# SCH_CatDoor_2024-03-03.net
KiCad netlist of a schematic drawn in EasyEDA
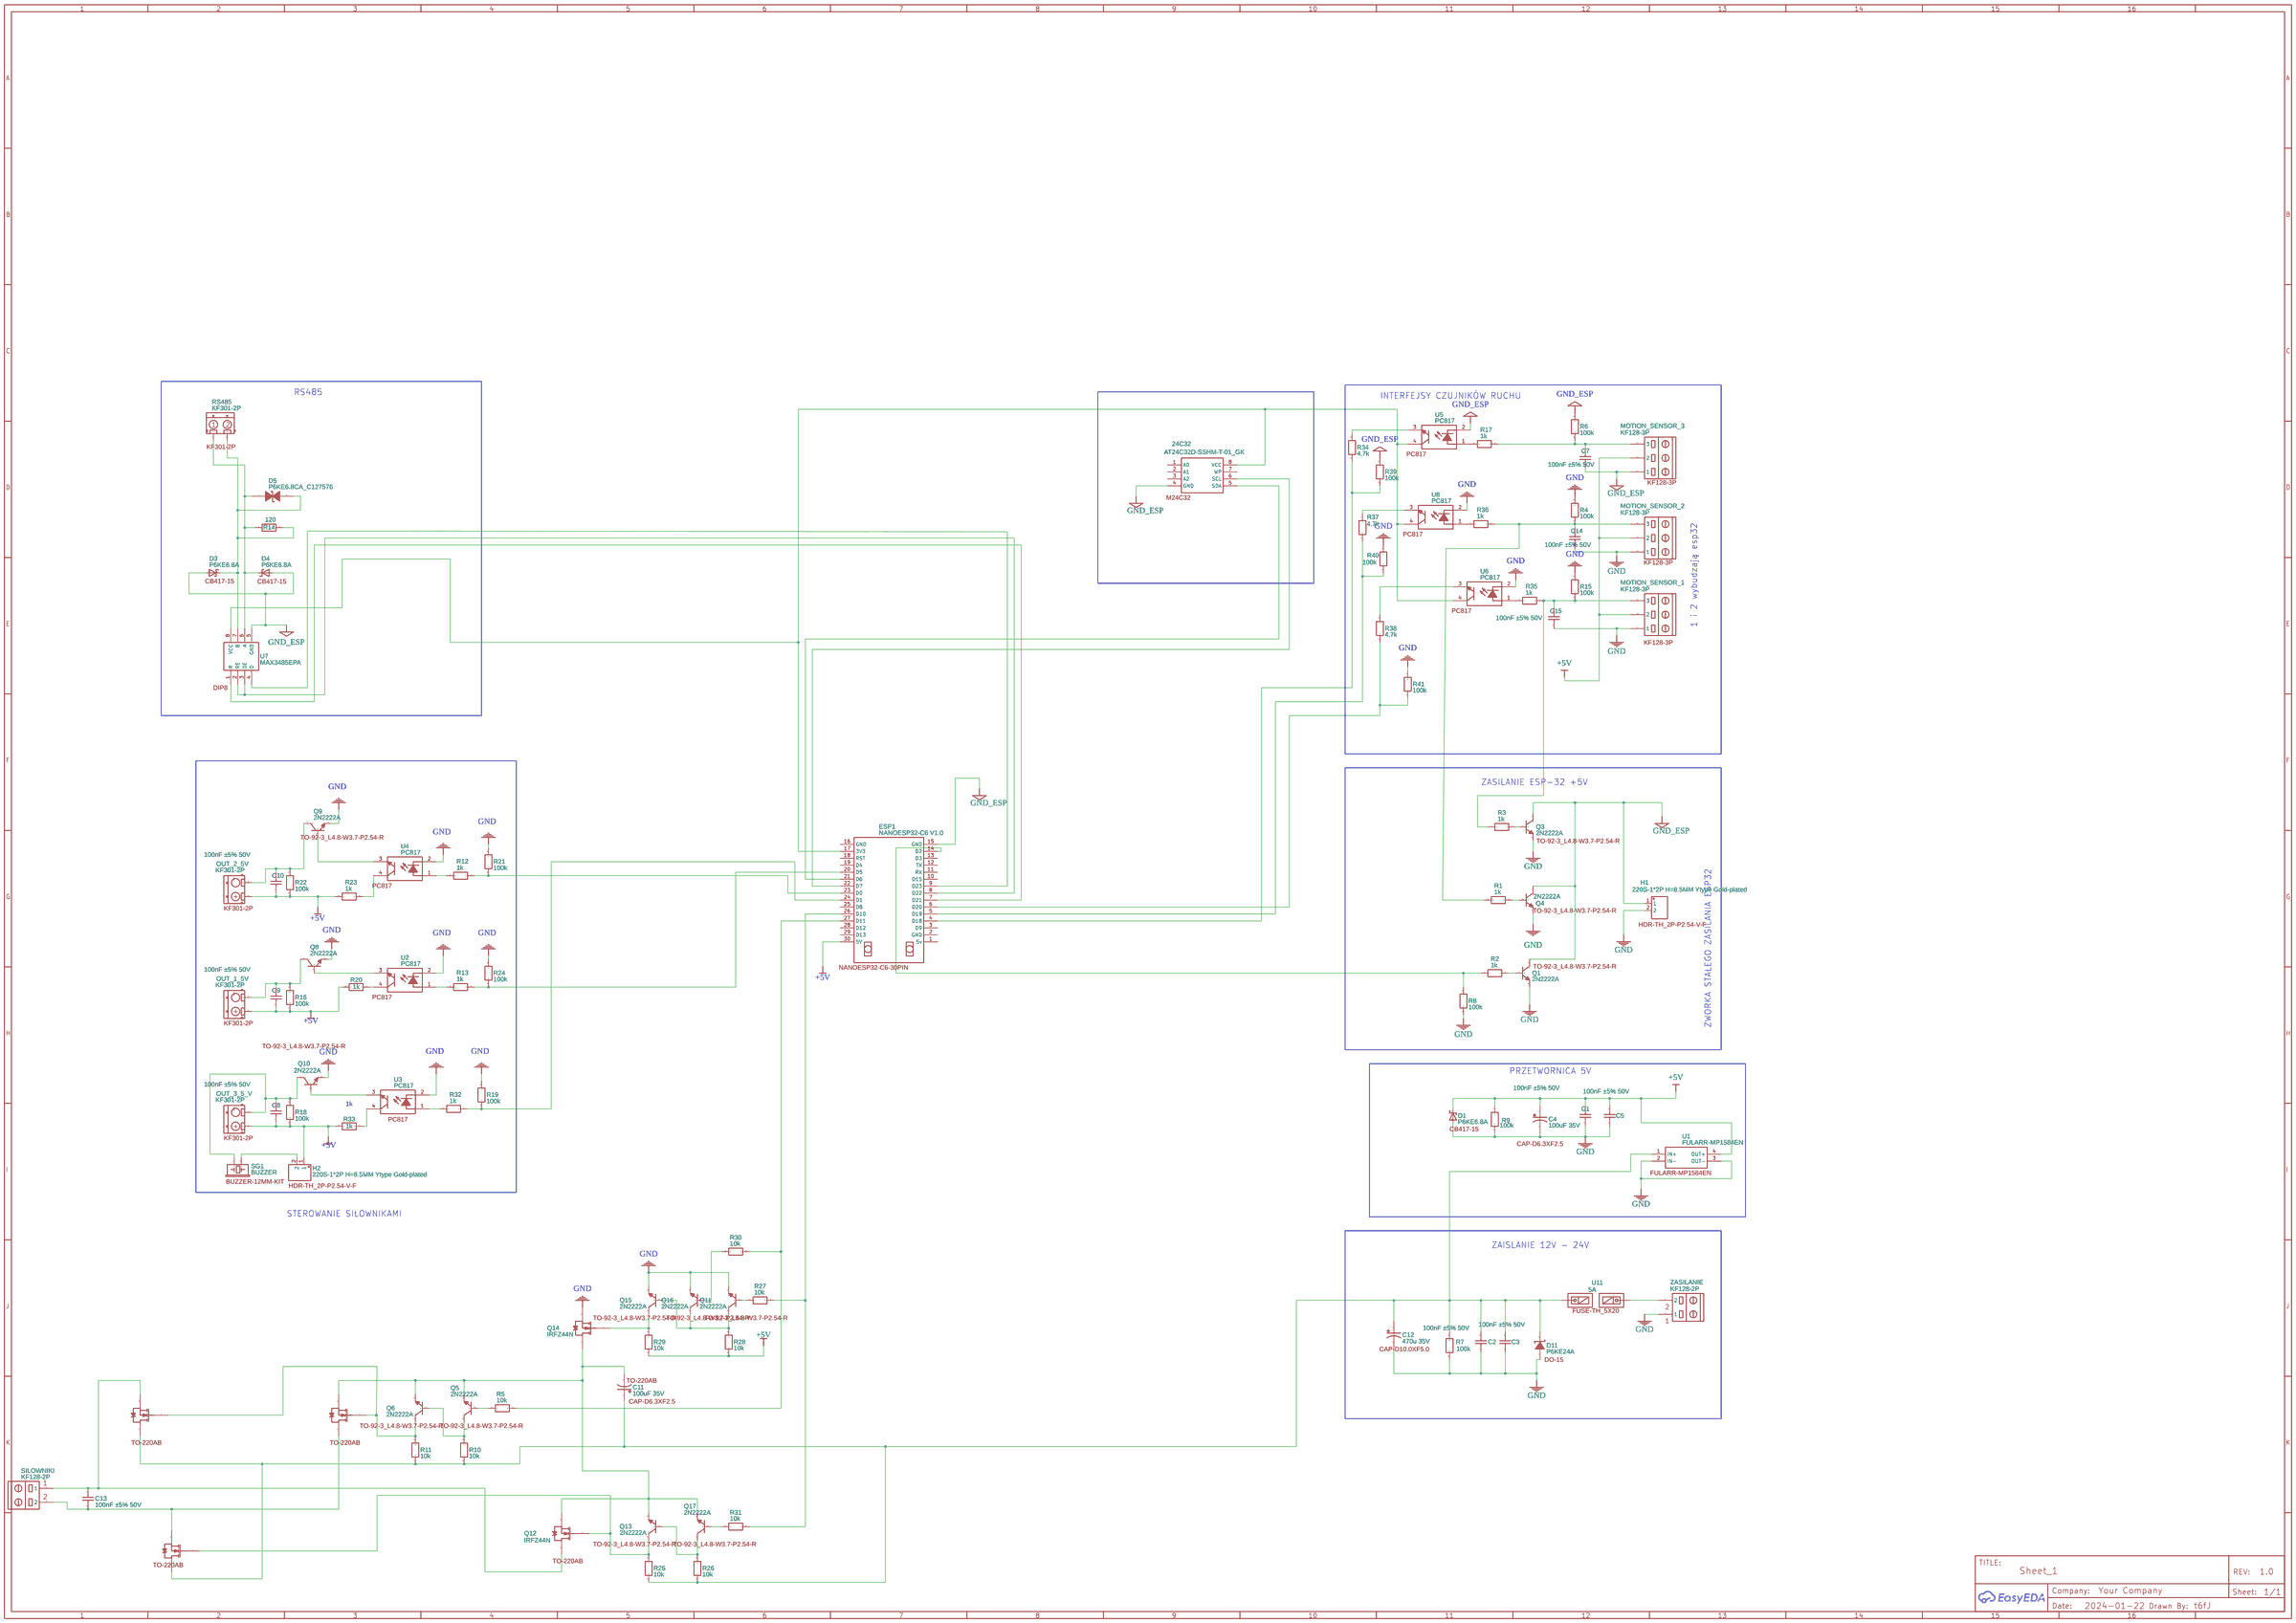
[diagram p0: schematic sheet]

(export (version "E")
  (design (tool "Eeschema 10.0.6"))
  (components
    (comp (ref "24C32")
      (value "AT24C32D-SSHM-T-01_GK")
      (fields (field (name "Manufacturer Part") "AT24C32D-SSHM-T") (field (name "Manufacturer") "MICROCHIP"))
      (libsource (lib "") (part "AT24C32D-SSHM-T-01_GK"))
    )
    (comp (ref "C1")
      (value "100nF ±5% 50V")
      (fields
        (field (name "Manufacturer Part") "10nF(103) ±5% 100V")
        (field (name "Manufacturer") "ReliaPro")
      )
      (libsource (lib "") (part "10nF(103) ±5% 100V"))
    )
    (comp (ref "C2")
      (value "100nF ±5% 50V")
      (fields
        (field (name "Manufacturer Part") "10nF(103) ±5% 100V")
        (field (name "Manufacturer") "ReliaPro")
      )
      (libsource (lib "") (part "10nF(103) ±5% 100V"))
    )
    (comp (ref "C3")
      (value "100nF ±5% 50V")
      (fields
        (field (name "Manufacturer Part") "10nF(103) ±5% 100V")
        (field (name "Manufacturer") "ReliaPro")
      )
      (libsource (lib "") (part "10nF(103) ±5% 100V"))
    )
    (comp (ref "C4") (value "100uF 35V") (libsource (lib "") (part "Cap_Electrolytic(TH)_D6.3XF2.5_US")))
    (comp (ref "C5")
      (value "100nF ±5% 50V")
      (fields
        (field (name "Manufacturer Part") "10nF(103) ±5% 100V")
        (field (name "Manufacturer") "ReliaPro")
      )
      (libsource (lib "") (part "10nF(103) ±5% 100V"))
    )
    (comp (ref "C7")
      (value "100nF ±5% 50V")
      (fields
        (field (name "Manufacturer Part") "10nF(103) ±5% 100V")
        (field (name "Manufacturer") "ReliaPro")
      )
      (libsource (lib "") (part "10nF(103) ±5% 100V"))
    )
    (comp (ref "C8")
      (value "100nF ±5% 50V")
      (fields
        (field (name "Manufacturer Part") "10nF(103) ±5% 100V")
        (field (name "Manufacturer") "ReliaPro")
      )
      (libsource (lib "") (part "10nF(103) ±5% 100V"))
    )
    (comp (ref "C9")
      (value "100nF ±5% 50V")
      (fields
        (field (name "Manufacturer Part") "10nF(103) ±5% 100V")
        (field (name "Manufacturer") "ReliaPro")
      )
      (libsource (lib "") (part "10nF(103) ±5% 100V"))
    )
    (comp (ref "C10")
      (value "100nF ±5% 50V")
      (fields
        (field (name "Manufacturer Part") "10nF(103) ±5% 100V")
        (field (name "Manufacturer") "ReliaPro")
      )
      (libsource (lib "") (part "10nF(103) ±5% 100V"))
    )
    (comp (ref "C11") (value "100uF 35V") (libsource (lib "") (part "Cap_Electrolytic(TH)_D6.3XF2.5_US_1")))
    (comp (ref "C12") (value "470u 35V") (libsource (lib "") (part "Cap_Electrolytic(TH)_D10.0XF5.0_US")))
    (comp (ref "C13")
      (value "100nF ±5% 50V")
      (fields
        (field (name "Manufacturer Part") "10nF(103) ±5% 100V")
        (field (name "Manufacturer") "ReliaPro")
      )
      (libsource (lib "") (part "10nF(103) ±5% 100V_1"))
    )
    (comp (ref "C14")
      (value "100nF ±5% 50V")
      (fields
        (field (name "Manufacturer Part") "10nF(103) ±5% 100V")
        (field (name "Manufacturer") "ReliaPro")
      )
      (libsource (lib "") (part "10nF(103) ±5% 100V"))
    )
    (comp (ref "C15")
      (value "100nF ±5% 50V")
      (fields
        (field (name "Manufacturer Part") "10nF(103) ±5% 100V")
        (field (name "Manufacturer") "ReliaPro")
      )
      (libsource (lib "") (part "10nF(103) ±5% 100V"))
    )
    (comp (ref "D1") (value "P6KE6.8A") (libsource (lib "") (part "P6KEXX")))
    (comp (ref "D3") (value "P6KE6.8A") (libsource (lib "") (part "P6KEXX_2")))
    (comp (ref "D4") (value "P6KE6.8A") (libsource (lib "") (part "P6KEXX_1")))
    (comp (ref "D5")
      (value "P6KE6.8CA_C127576")
      (fields (field (name "Manufacturer Part") "P6KE6.8CA") (field (name "Manufacturer") "Yenji"))
      (libsource (lib "") (part "P6KE6.8CA_C127576"))
    )
    (comp (ref "D11")
      (value "P6KE24A")
      (fields (field (name "Manufacturer Part") "P6KE30A") (field (name "Manufacturer") "STMicroelectronics"))
      (libsource (lib "") (part "P6KE30A_C133726"))
    )
    (comp (ref "ESP1") (value "NANOESP32-C6 V1.0") (libsource (lib "") (part "NANOESP32-C6 V1.0")))
    (comp (ref "H1")
      (value "220S-1*2P H=8.5MM Ytype Gold-plated")
      (fields (field (name "Manufacturer Part") "B-2200S02P-A120") (field (name "Manufacturer") "Ckmtw(灿科盟)"))
      (libsource (lib "") (part "220S-1*2P H=8.5MM Ytype Gold-plated_1"))
    )
    (comp (ref "H2")
      (value "220S-1*2P H=8.5MM Ytype Gold-plated")
      (fields (field (name "Manufacturer Part") "B-2200S02P-A120") (field (name "Manufacturer") "Ckmtw(灿科盟)"))
      (libsource (lib "") (part "220S-1*2P H=8.5MM Ytype Gold-plated"))
    )
    (comp (ref "MOTION_SENSOR_1")
      (value "KF128-3P")
      (fields (field (name "Manufacturer Part") "P?"))
      (libsource (lib "") (part "KF128-3P"))
    )
    (comp (ref "MOTION_SENSOR_2")
      (value "KF128-3P")
      (fields (field (name "Manufacturer Part") "P?"))
      (libsource (lib "") (part "KF128-3P_1"))
    )
    (comp (ref "MOTION_SENSOR_3")
      (value "KF128-3P")
      (fields (field (name "Manufacturer Part") "P?"))
      (libsource (lib "") (part "KF128-3P_2"))
    )
    (comp (ref "OUT_1_5V") (value "KF301-2P") (libsource (lib "") (part "KF301-2P")))
    (comp (ref "OUT_2_5V") (value "KF301-2P") (libsource (lib "") (part "KF301-2P_3")))
    (comp (ref "OUT_3_5_V") (value "KF301-2P") (libsource (lib "") (part "KF301-2P_2")))
    (comp (ref "Q1")
      (value "2N2222A")
      (fields (field (name "Manufacturer") "Foshan Blue Rocket Elec"))
      (libsource (lib "") (part "2N2222A"))
    )
    (comp (ref "Q2") (value "IRFZ44N") (libsource (lib "") (part "IRF1404_1")))
    (comp (ref "Q3")
      (value "2N2222A")
      (fields (field (name "Manufacturer") "Foshan Blue Rocket Elec"))
      (libsource (lib "") (part "2N2222A_6"))
    )
    (comp (ref "Q4")
      (value "2N2222A")
      (fields (field (name "Manufacturer") "Foshan Blue Rocket Elec"))
      (libsource (lib "") (part "2N2222A_5"))
    )
    (comp (ref "Q5")
      (value "2N2222A")
      (fields (field (name "Manufacturer") "Foshan Blue Rocket Elec"))
      (libsource (lib "") (part "2N2222A_1"))
    )
    (comp (ref "Q6")
      (value "2N2222A")
      (fields (field (name "Manufacturer") "Foshan Blue Rocket Elec"))
      (libsource (lib "") (part "2N2222A_3"))
    )
    (comp (ref "Q7") (value "IRFZ44N") (libsource (lib "") (part "IRF1404_1")))
    (comp (ref "Q8")
      (value "2N2222A")
      (fields (field (name "Manufacturer") "Foshan Blue Rocket Elec"))
      (libsource (lib "") (part "2N2222A_7"))
    )
    (comp (ref "Q9")
      (value "2N2222A")
      (fields (field (name "Manufacturer") "Foshan Blue Rocket Elec"))
      (libsource (lib "") (part "2N2222A_2"))
    )
    (comp (ref "Q10")
      (value "2N2222A")
      (fields (field (name "Manufacturer") "Foshan Blue Rocket Elec"))
      (libsource (lib "") (part "2N2222A_4"))
    )
    (comp (ref "Q11")
      (value "2N2222A")
      (fields (field (name "Manufacturer") "Foshan Blue Rocket Elec"))
      (libsource (lib "") (part "2N2222A_1"))
    )
    (comp (ref "Q12") (value "IRFZ44N") (libsource (lib "") (part "IRF1404_1")))
    (comp (ref "Q13")
      (value "2N2222A")
      (fields (field (name "Manufacturer") "Foshan Blue Rocket Elec"))
      (libsource (lib "") (part "2N2222A_3"))
    )
    (comp (ref "Q14") (value "IRFZ44N") (libsource (lib "") (part "IRF1404_2")))
    (comp (ref "Q15")
      (value "2N2222A")
      (fields (field (name "Manufacturer") "Foshan Blue Rocket Elec"))
      (libsource (lib "") (part "2N2222A_3"))
    )
    (comp (ref "Q16")
      (value "2N2222A")
      (fields (field (name "Manufacturer") "Foshan Blue Rocket Elec"))
      (libsource (lib "") (part "2N2222A_1"))
    )
    (comp (ref "Q17")
      (value "2N2222A")
      (fields (field (name "Manufacturer") "Foshan Blue Rocket Elec"))
      (libsource (lib "") (part "2N2222A_1"))
    )
    (comp (ref "Q18") (value "IRFZ44N") (libsource (lib "") (part "IRF1404")))
    (comp (ref "R1") (value "1k") (libsource (lib "") (part "R_AXIAL-0.3_EU_1")))
    (comp (ref "R2") (value "1k") (libsource (lib "") (part "R_AXIAL-0.3_EU_1")))
    (comp (ref "R3") (value "1k") (libsource (lib "") (part "R_AXIAL-0.3_EU_1")))
    (comp (ref "R4") (value "100k") (libsource (lib "") (part "R_AXIAL-0.3_EU")))
    (comp (ref "R5") (value "10k") (libsource (lib "") (part "R_AXIAL-0.3_EU_3")))
    (comp (ref "R6") (value "100k") (libsource (lib "") (part "R_AXIAL-0.3_EU")))
    (comp (ref "R7") (value "100k") (libsource (lib "") (part "R_AXIAL-0.3_EU_2")))
    (comp (ref "R8") (value "100k") (libsource (lib "") (part "R_AXIAL-0.3_EU_2")))
    (comp (ref "R9") (value "100k") (libsource (lib "") (part "R_AXIAL-0.3_EU_2")))
    (comp (ref "R10") (value "10k") (libsource (lib "") (part "R_AXIAL-0.3_EU")))
    (comp (ref "R11") (value "10k") (libsource (lib "") (part "R_AXIAL-0.3_EU")))
    (comp (ref "R12") (value "1k") (libsource (lib "") (part "R_AXIAL-0.3_EU_1")))
    (comp (ref "R13") (value "1k") (libsource (lib "") (part "R_AXIAL-0.3_EU_1")))
    (comp (ref "R14") (value "120") (libsource (lib "") (part "R_AXIAL-0.3_EU_3")))
    (comp (ref "R15") (value "100k") (libsource (lib "") (part "R_AXIAL-0.3_EU")))
    (comp (ref "R16") (value "100k") (libsource (lib "") (part "R_AXIAL-0.3_EU_2")))
    (comp (ref "R17") (value "1k") (libsource (lib "") (part "R_AXIAL-0.3_EU_1")))
    (comp (ref "R18") (value "100k") (libsource (lib "") (part "R_AXIAL-0.3_EU_2")))
    (comp (ref "R19") (value "100k") (libsource (lib "") (part "R_AXIAL-0.3_EU_2")))
    (comp (ref "R20") (value "1k") (libsource (lib "") (part "R_AXIAL-0.3_EU_1")))
    (comp (ref "R21") (value "100k") (libsource (lib "") (part "R_AXIAL-0.3_EU_2")))
    (comp (ref "R22") (value "100k") (libsource (lib "") (part "R_AXIAL-0.3_EU_2")))
    (comp (ref "R23") (value "1k") (libsource (lib "") (part "R_AXIAL-0.3_EU_1")))
    (comp (ref "R24") (value "100k") (libsource (lib "") (part "R_AXIAL-0.3_EU_2")))
    (comp (ref "R25") (value "10k") (libsource (lib "") (part "R_AXIAL-0.3_EU")))
    (comp (ref "R26") (value "10k") (libsource (lib "") (part "R_AXIAL-0.3_EU")))
    (comp (ref "R27") (value "10k") (libsource (lib "") (part "R_AXIAL-0.3_EU_3")))
    (comp (ref "R28") (value "10k") (libsource (lib "") (part "R_AXIAL-0.3_EU")))
    (comp (ref "R29") (value "10k") (libsource (lib "") (part "R_AXIAL-0.3_EU")))
    (comp (ref "R30") (value "10k") (libsource (lib "") (part "R_AXIAL-0.3_EU_3")))
    (comp (ref "R31") (value "10k") (libsource (lib "") (part "R_AXIAL-0.3_EU_3")))
    (comp (ref "R32") (value "1k") (libsource (lib "") (part "R_AXIAL-0.3_EU_1")))
    (comp (ref "R33") (value "1k") (libsource (lib "") (part "R_AXIAL-0.3_EU_1")))
    (comp (ref "R34") (value "4,7k") (libsource (lib "") (part "R_AXIAL-0.3_EU_2")))
    (comp (ref "R35") (value "1k") (libsource (lib "") (part "R_AXIAL-0.3_EU_1")))
    (comp (ref "R36") (value "1k") (libsource (lib "") (part "R_AXIAL-0.3_EU_1")))
    (comp (ref "R37") (value "4,7k") (libsource (lib "") (part "R_AXIAL-0.3_EU_2")))
    (comp (ref "R38") (value "4,7k") (libsource (lib "") (part "R_AXIAL-0.3_EU_2")))
    (comp (ref "R39") (value "100k") (libsource (lib "") (part "R_AXIAL-0.3_EU")))
    (comp (ref "R40") (value "100k") (libsource (lib "") (part "R_AXIAL-0.3_EU")))
    (comp (ref "R41") (value "100k") (libsource (lib "") (part "R_AXIAL-0.3_EU")))
    (comp (ref "RS485") (value "KF301-2P") (libsource (lib "") (part "KF301-2P_1")))
    (comp (ref "SG1") (value "BUZZER") (libsource (lib "") (part "BUZZER")))
    (comp (ref "SILOWNIKI") (value "KF128-2P") (libsource (lib "") (part "KF128-2P")))
    (comp (ref "U1") (value "FULARR-MP1584EN") (libsource (lib "") (part "FULARR-MP1584EN")))
    (comp (ref "U2")
      (value "PC817")
      (fields
        (field (name "Manufacturer Part") "PC817X1NSZ2B")
        (field (name "Manufacturer") "Sharp Microelectronics")
      )
      (libsource (lib "") (part "PC817"))
    )
    (comp (ref "U3")
      (value "PC817")
      (fields
        (field (name "Manufacturer Part") "PC817X1NSZ2B")
        (field (name "Manufacturer") "Sharp Microelectronics")
      )
      (libsource (lib "") (part "PC817_1"))
    )
    (comp (ref "U4")
      (value "PC817")
      (fields
        (field (name "Manufacturer Part") "PC817X1NSZ2B")
        (field (name "Manufacturer") "Sharp Microelectronics")
      )
      (libsource (lib "") (part "PC817"))
    )
    (comp (ref "U5")
      (value "PC817")
      (fields
        (field (name "Manufacturer Part") "PC817X1NSZ2B")
        (field (name "Manufacturer") "Sharp Microelectronics")
      )
      (libsource (lib "") (part "PC817"))
    )
    (comp (ref "U6")
      (value "PC817")
      (fields
        (field (name "Manufacturer Part") "PC817X1NSZ2B")
        (field (name "Manufacturer") "Sharp Microelectronics")
      )
      (libsource (lib "") (part "PC817"))
    )
    (comp (ref "U7") (value "MAX3485EPA") (libsource (lib "") (part "MAX485")))
    (comp (ref "U8")
      (value "PC817")
      (fields
        (field (name "Manufacturer Part") "PC817X1NSZ2B")
        (field (name "Manufacturer") "Sharp Microelectronics")
      )
      (libsource (lib "") (part "PC817"))
    )
    (comp (ref "U11")
      (value "5A")
      (fields
        (field (name "Manufacturer Part") "5x20 RHOS Fuse clip/seat")
        (field (name "Manufacturer") "XCFuse")
      )
      (libsource (lib "") (part "FUSE_5x20"))
    )
    (comp (ref "ZASILANIE") (value "KF128-2P") (libsource (lib "") (part "KF128-2P_1")))
  )
  (nets
    (net (code "1") (name "+5V") (class "Default")
      (node (ref "C1") (pin "2") (pinfunction "2_2") (pintype "input"))
      (node (ref "C10") (pin "1") (pinfunction "1_1") (pintype "input"))
      (node (ref "C4") (pin "1") (pinfunction "1_1") (pintype "unspecified"))
      (node (ref "C5") (pin "2") (pinfunction "2_2") (pintype "input"))
      (node (ref "C8") (pin "1") (pinfunction "1_1") (pintype "input"))
      (node (ref "C9") (pin "1") (pinfunction "1_1") (pintype "input"))
      (node (ref "D1") (pin "C") (pinfunction "C_C") (pintype "bidirectional"))
      (node (ref "ESP1") (pin "30") (pinfunction "5V_30") (pintype "unspecified"))
      (node (ref "H2") (pin "1") (pinfunction "1_1") (pintype "unspecified"))
      (node (ref "MOTION_SENSOR_1") (pin "2") (pinfunction "2_2") (pintype "unspecified"))
      (node (ref "MOTION_SENSOR_2") (pin "2") (pinfunction "2_2") (pintype "unspecified"))
      (node (ref "MOTION_SENSOR_3") (pin "2") (pinfunction "2_2") (pintype "unspecified"))
      (node (ref "OUT_1_5V") (pin "1") (pinfunction "1_1") (pintype "unspecified"))
      (node (ref "OUT_2_5V") (pin "1") (pinfunction "1_1") (pintype "unspecified"))
      (node (ref "OUT_3_5_V") (pin "1") (pinfunction "1_1") (pintype "unspecified"))
      (node (ref "R16") (pin "2") (pinfunction "2_2") (pintype "unspecified"))
      (node (ref "R18") (pin "2") (pinfunction "2_2") (pintype "unspecified"))
      (node (ref "R20") (pin "2") (pinfunction "2_2") (pintype "unspecified"))
      (node (ref "R22") (pin "2") (pinfunction "2_2") (pintype "unspecified"))
      (node (ref "R23") (pin "2") (pinfunction "2_2") (pintype "unspecified"))
      (node (ref "R28") (pin "1") (pinfunction "1_1") (pintype "unspecified"))
      (node (ref "R29") (pin "1") (pinfunction "1_1") (pintype "unspecified"))
      (node (ref "R33") (pin "2") (pinfunction "2_2") (pintype "unspecified"))
      (node (ref "R9") (pin "1") (pinfunction "1_1") (pintype "unspecified"))
      (node (ref "U1") (pin "4") (pinfunction "OUT+_4") (pintype "unspecified"))
    )
    (net (code "2") (name "GND") (class "Default")
      (node (ref "C1") (pin "1") (pinfunction "1_1") (pintype "input"))
      (node (ref "C12") (pin "2") (pinfunction "2_2") (pintype "unspecified"))
      (node (ref "C14") (pin "1") (pinfunction "1_1") (pintype "input"))
      (node (ref "C15") (pin "1") (pinfunction "1_1") (pintype "input"))
      (node (ref "C2") (pin "1") (pinfunction "1_1") (pintype "input"))
      (node (ref "C3") (pin "1") (pinfunction "1_1") (pintype "input"))
      (node (ref "C4") (pin "2") (pinfunction "2_2") (pintype "unspecified"))
      (node (ref "C5") (pin "1") (pinfunction "1_1") (pintype "input"))
      (node (ref "D1") (pin "A") (pinfunction "A_A") (pintype "bidirectional"))
      (node (ref "D11") (pin "1") (pinfunction "A_1") (pintype "unspecified"))
      (node (ref "H1") (pin "2") (pinfunction "2_2") (pintype "unspecified"))
      (node (ref "MOTION_SENSOR_1") (pin "1") (pinfunction "1_1") (pintype "unspecified"))
      (node (ref "MOTION_SENSOR_2") (pin "1") (pinfunction "1_1") (pintype "unspecified"))
      (node (ref "Q1") (pin "3") (pinfunction "E_3") (pintype "unspecified"))
      (node (ref "Q10") (pin "3") (pinfunction "E_3") (pintype "unspecified"))
      (node (ref "Q11") (pin "3") (pinfunction "E_3") (pintype "unspecified"))
      (node (ref "Q14") (pin "3") (pinfunction "S_3") (pintype "unspecified"))
      (node (ref "Q15") (pin "3") (pinfunction "E_3") (pintype "unspecified"))
      (node (ref "Q16") (pin "3") (pinfunction "E_3") (pintype "unspecified"))
      (node (ref "Q3") (pin "3") (pinfunction "E_3") (pintype "unspecified"))
      (node (ref "Q4") (pin "3") (pinfunction "E_3") (pintype "unspecified"))
      (node (ref "Q8") (pin "3") (pinfunction "E_3") (pintype "unspecified"))
      (node (ref "Q9") (pin "3") (pinfunction "E_3") (pintype "unspecified"))
      (node (ref "R15") (pin "2") (pinfunction "2_2") (pintype "unspecified"))
      (node (ref "R19") (pin "1") (pinfunction "1_1") (pintype "unspecified"))
      (node (ref "R21") (pin "1") (pinfunction "1_1") (pintype "unspecified"))
      (node (ref "R24") (pin "1") (pinfunction "1_1") (pintype "unspecified"))
      (node (ref "R4") (pin "2") (pinfunction "2_2") (pintype "unspecified"))
      (node (ref "R40") (pin "2") (pinfunction "2_2") (pintype "unspecified"))
      (node (ref "R41") (pin "2") (pinfunction "2_2") (pintype "unspecified"))
      (node (ref "R7") (pin "2") (pinfunction "2_2") (pintype "unspecified"))
      (node (ref "R8") (pin "2") (pinfunction "2_2") (pintype "unspecified"))
      (node (ref "R9") (pin "2") (pinfunction "2_2") (pintype "unspecified"))
      (node (ref "U1") (pin "2") (pinfunction "IN-_2") (pintype "unspecified"))
      (node (ref "U1") (pin "3") (pinfunction "OUT-_3") (pintype "unspecified"))
      (node (ref "U2") (pin "2") (pinfunction "2_2") (pintype "unspecified"))
      (node (ref "U3") (pin "2") (pinfunction "2_2") (pintype "unspecified"))
      (node (ref "U4") (pin "2") (pinfunction "2_2") (pintype "unspecified"))
      (node (ref "U6") (pin "2") (pinfunction "2_2") (pintype "unspecified"))
      (node (ref "U8") (pin "2") (pinfunction "2_2") (pintype "unspecified"))
      (node (ref "ZASILANIE") (pin "1") (pinfunction "1_1") (pintype "unspecified"))
    )
    (net (code "3") (name "GND_ESP") (class "Default")
      (node (ref "24C32") (pin "4") (pinfunction "GND_4") (pintype "unspecified"))
      (node (ref "C7") (pin "1") (pinfunction "1_1") (pintype "input"))
      (node (ref "D3") (pin "A") (pinfunction "A_A") (pintype "bidirectional"))
      (node (ref "D4") (pin "A") (pinfunction "A_A") (pintype "bidirectional"))
      (node (ref "ESP1") (pin "15") (pinfunction "GND_15") (pintype "unspecified"))
      (node (ref "H1") (pin "1") (pinfunction "1_1") (pintype "unspecified"))
      (node (ref "MOTION_SENSOR_3") (pin "1") (pinfunction "1_1") (pintype "unspecified"))
      (node (ref "Q1") (pin "1") (pinfunction "C_1") (pintype "unspecified"))
      (node (ref "Q3") (pin "1") (pinfunction "C_1") (pintype "unspecified"))
      (node (ref "Q4") (pin "1") (pinfunction "C_1") (pintype "unspecified"))
      (node (ref "R39") (pin "2") (pinfunction "2_2") (pintype "unspecified"))
      (node (ref "R6") (pin "2") (pinfunction "2_2") (pintype "unspecified"))
      (node (ref "U5") (pin "2") (pinfunction "2_2") (pintype "unspecified"))
      (node (ref "U7") (pin "5") (pinfunction "GND_5") (pintype "unspecified"))
    )
    (net (code "4") (name "Net-(24C32-SCL)") (class "Default")
      (node (ref "24C32") (pin "6") (pinfunction "SCL_6") (pintype "unspecified"))
      (node (ref "ESP1") (pin "22") (pinfunction "D7_22") (pintype "unspecified"))
    )
    (net (code "5") (name "Net-(24C32-SDA)") (class "Default")
      (node (ref "24C32") (pin "5") (pinfunction "SDA_5") (pintype "unspecified"))
      (node (ref "ESP1") (pin "21") (pinfunction "D6_21") (pintype "unspecified"))
    )
    (net (code "6") (name "Net-(24C32-VCC)") (class "Default")
      (node (ref "24C32") (pin "8") (pinfunction "VCC_8") (pintype "unspecified"))
      (node (ref "ESP1") (pin "17") (pinfunction "3V3_17") (pintype "unspecified"))
      (node (ref "U5") (pin "4") (pinfunction "4_4") (pintype "unspecified"))
      (node (ref "U6") (pin "4") (pinfunction "4_4") (pintype "unspecified"))
      (node (ref "U7") (pin "8") (pinfunction "VCC_8") (pintype "unspecified"))
      (node (ref "U8") (pin "4") (pinfunction "4_4") (pintype "unspecified"))
    )
    (net (code "7") (name "Net-(C7-Pad2)") (class "Default")
      (node (ref "C7") (pin "2") (pinfunction "2_2") (pintype "input"))
      (node (ref "MOTION_SENSOR_3") (pin "3") (pinfunction "3_3") (pintype "unspecified"))
      (node (ref "R17") (pin "1") (pinfunction "1_1") (pintype "unspecified"))
      (node (ref "R6") (pin "1") (pinfunction "1_1") (pintype "unspecified"))
    )
    (net (code "8") (name "Net-(C14-Pad2)") (class "Default")
      (node (ref "C14") (pin "2") (pinfunction "2_2") (pintype "input"))
      (node (ref "MOTION_SENSOR_2") (pin "3") (pinfunction "3_3") (pintype "unspecified"))
      (node (ref "R1") (pin "2") (pinfunction "2_2") (pintype "unspecified"))
      (node (ref "R36") (pin "1") (pinfunction "1_1") (pintype "unspecified"))
      (node (ref "R4") (pin "1") (pinfunction "1_1") (pintype "unspecified"))
    )
    (net (code "9") (name "Net-(C15-Pad2)") (class "Default")
      (node (ref "C15") (pin "2") (pinfunction "2_2") (pintype "input"))
      (node (ref "MOTION_SENSOR_1") (pin "3") (pinfunction "3_3") (pintype "unspecified"))
      (node (ref "R15") (pin "1") (pinfunction "1_1") (pintype "unspecified"))
      (node (ref "R3") (pin "2") (pinfunction "2_2") (pintype "unspecified"))
      (node (ref "R35") (pin "1") (pinfunction "1_1") (pintype "unspecified"))
    )
    (net (code "10") (name "Net-(D11-K)") (class "Default")
      (node (ref "C11") (pin "1") (pinfunction "1_1") (pintype "unspecified"))
      (node (ref "C12") (pin "1") (pinfunction "1_1") (pintype "unspecified"))
      (node (ref "C2") (pin "2") (pinfunction "2_2") (pintype "input"))
      (node (ref "C3") (pin "2") (pinfunction "2_2") (pintype "input"))
      (node (ref "D11") (pin "2") (pinfunction "K_2") (pintype "unspecified"))
      (node (ref "Q18") (pin "2") (pinfunction "D_2") (pintype "unspecified"))
      (node (ref "Q7") (pin "2") (pinfunction "D_2") (pintype "unspecified"))
      (node (ref "R10") (pin "1") (pinfunction "1_1") (pintype "unspecified"))
      (node (ref "R11") (pin "1") (pinfunction "1_1") (pintype "unspecified"))
      (node (ref "R25") (pin "1") (pinfunction "1_1") (pintype "unspecified"))
      (node (ref "R26") (pin "1") (pinfunction "1_1") (pintype "unspecified"))
      (node (ref "R7") (pin "1") (pinfunction "1_1") (pintype "unspecified"))
      (node (ref "U1") (pin "1") (pinfunction "IN+_1") (pintype "unspecified"))
      (node (ref "U11") (pin "1") (pinfunction "1_1") (pintype "unspecified"))
    )
    (net (code "11") (name "Net-(ESP1-D0)") (class "Default")
      (node (ref "ESP1") (pin "23") (pinfunction "D0_23") (pintype "unspecified"))
      (node (ref "R12") (pin "1") (pinfunction "1_1") (pintype "unspecified"))
      (node (ref "R21") (pin "2") (pinfunction "2_2") (pintype "unspecified"))
    )
    (net (code "12") (name "Net-(ESP1-D1)") (class "Default")
      (node (ref "ESP1") (pin "24") (pinfunction "D1_24") (pintype "unspecified"))
      (node (ref "R19") (pin "2") (pinfunction "2_2") (pintype "unspecified"))
      (node (ref "R32") (pin "1") (pinfunction "1_1") (pintype "unspecified"))
    )
    (net (code "13") (name "Net-(ESP1-D2)") (class "Default")
      (node (ref "ESP1") (pin "14") (pinfunction "D2_14") (pintype "unspecified"))
      (node (ref "R2") (pin "2") (pinfunction "2_2") (pintype "unspecified"))
      (node (ref "R8") (pin "1") (pinfunction "1_1") (pintype "unspecified"))
    )
    (net (code "14") (name "Net-(ESP1-D5)") (class "Default")
      (node (ref "ESP1") (pin "20") (pinfunction "D5_20") (pintype "unspecified"))
      (node (ref "R13") (pin "1") (pinfunction "1_1") (pintype "unspecified"))
      (node (ref "R24") (pin "2") (pinfunction "2_2") (pintype "unspecified"))
    )
    (net (code "15") (name "Net-(ESP1-D10)") (class "Default")
      (node (ref "ESP1") (pin "26") (pinfunction "D10_26") (pintype "unspecified"))
      (node (ref "R27") (pin "2") (pinfunction "2_2") (pintype "unspecified"))
      (node (ref "R31") (pin "2") (pinfunction "2_2") (pintype "unspecified"))
    )
    (net (code "16") (name "Net-(ESP1-D11)") (class "Default")
      (node (ref "ESP1") (pin "27") (pinfunction "D11_27") (pintype "unspecified"))
      (node (ref "R30") (pin "2") (pinfunction "2_2") (pintype "unspecified"))
      (node (ref "R5") (pin "2") (pinfunction "2_2") (pintype "unspecified"))
    )
    (net (code "17") (name "Net-(ESP1-D18)") (class "Default")
      (node (ref "ESP1") (pin "4") (pinfunction "D18_4") (pintype "unspecified"))
      (node (ref "R34") (pin "2") (pinfunction "2_2") (pintype "unspecified"))
      (node (ref "R39") (pin "1") (pinfunction "1_1") (pintype "unspecified"))
    )
    (net (code "18") (name "Net-(ESP1-D19)") (class "Default")
      (node (ref "ESP1") (pin "5") (pinfunction "D19_5") (pintype "unspecified"))
      (node (ref "R37") (pin "2") (pinfunction "2_2") (pintype "unspecified"))
      (node (ref "R40") (pin "1") (pinfunction "1_1") (pintype "unspecified"))
    )
    (net (code "19") (name "Net-(ESP1-D20)") (class "Default")
      (node (ref "ESP1") (pin "6") (pinfunction "D20_6") (pintype "unspecified"))
      (node (ref "R38") (pin "2") (pinfunction "2_2") (pintype "unspecified"))
      (node (ref "R41") (pin "1") (pinfunction "1_1") (pintype "unspecified"))
    )
    (net (code "20") (name "Net-(ESP1-D21)") (class "Default")
      (node (ref "ESP1") (pin "7") (pinfunction "D21_7") (pintype "unspecified"))
      (node (ref "U7") (pin "1") (pinfunction "R_1") (pintype "unspecified"))
    )
    (net (code "21") (name "Net-(ESP1-D22)") (class "Default")
      (node (ref "ESP1") (pin "8") (pinfunction "D22_8") (pintype "unspecified"))
      (node (ref "U7") (pin "2") (pinfunction "RE_2") (pintype "unspecified"))
      (node (ref "U7") (pin "3") (pinfunction "DE_3") (pintype "unspecified"))
    )
    (net (code "22") (name "Net-(ESP1-D23)") (class "Default")
      (node (ref "ESP1") (pin "9") (pinfunction "D23_9") (pintype "unspecified"))
      (node (ref "U7") (pin "4") (pinfunction "D_4") (pintype "unspecified"))
    )
    (net (code "23") (name "Net-(Q1-B)") (class "Default")
      (node (ref "Q1") (pin "2") (pinfunction "B_2") (pintype "unspecified"))
      (node (ref "R2") (pin "1") (pinfunction "1_1") (pintype "unspecified"))
    )
    (net (code "24") (name "Net-(Q2-G)") (class "Default")
      (node (ref "Q2") (pin "1") (pinfunction "G_1") (pintype "unspecified"))
      (node (ref "Q6") (pin "1") (pinfunction "C_1") (pintype "unspecified"))
      (node (ref "Q7") (pin "1") (pinfunction "G_1") (pintype "unspecified"))
      (node (ref "R11") (pin "2") (pinfunction "2_2") (pintype "unspecified"))
    )
    (net (code "25") (name "Net-(Q3-B)") (class "Default")
      (node (ref "Q3") (pin "2") (pinfunction "B_2") (pintype "unspecified"))
      (node (ref "R3") (pin "1") (pinfunction "1_1") (pintype "unspecified"))
    )
    (net (code "26") (name "Net-(Q4-B)") (class "Default")
      (node (ref "Q4") (pin "2") (pinfunction "B_2") (pintype "unspecified"))
      (node (ref "R1") (pin "1") (pinfunction "1_1") (pintype "unspecified"))
    )
    (net (code "27") (name "Net-(Q5-B)") (class "Default")
      (node (ref "Q5") (pin "2") (pinfunction "B_2") (pintype "unspecified"))
      (node (ref "R5") (pin "1") (pinfunction "1_1") (pintype "unspecified"))
    )
    (net (code "28") (name "Net-(Q5-C)") (class "Default")
      (node (ref "Q5") (pin "1") (pinfunction "C_1") (pintype "unspecified"))
      (node (ref "Q6") (pin "2") (pinfunction "B_2") (pintype "unspecified"))
      (node (ref "R10") (pin "2") (pinfunction "2_2") (pintype "unspecified"))
    )
    (net (code "29") (name "Net-(Q8-B)") (class "Default")
      (node (ref "Q8") (pin "2") (pinfunction "B_2") (pintype "unspecified"))
      (node (ref "U2") (pin "3") (pinfunction "3_3") (pintype "unspecified"))
    )
    (net (code "30") (name "Net-(Q8-C)") (class "Default")
      (node (ref "C9") (pin "2") (pinfunction "2_2") (pintype "input"))
      (node (ref "OUT_1_5V") (pin "2") (pinfunction "2_2") (pintype "unspecified"))
      (node (ref "Q8") (pin "1") (pinfunction "C_1") (pintype "unspecified"))
      (node (ref "R16") (pin "1") (pinfunction "1_1") (pintype "unspecified"))
    )
    (net (code "31") (name "Net-(Q9-B)") (class "Default")
      (node (ref "Q9") (pin "2") (pinfunction "B_2") (pintype "unspecified"))
      (node (ref "U4") (pin "3") (pinfunction "3_3") (pintype "unspecified"))
    )
    (net (code "32") (name "Net-(Q9-C)") (class "Default")
      (node (ref "C10") (pin "2") (pinfunction "2_2") (pintype "input"))
      (node (ref "OUT_2_5V") (pin "2") (pinfunction "2_2") (pintype "unspecified"))
      (node (ref "Q9") (pin "1") (pinfunction "C_1") (pintype "unspecified"))
      (node (ref "R22") (pin "1") (pinfunction "1_1") (pintype "unspecified"))
    )
    (net (code "33") (name "Net-(Q10-B)") (class "Default")
      (node (ref "Q10") (pin "2") (pinfunction "B_2") (pintype "unspecified"))
      (node (ref "U3") (pin "3") (pinfunction "3_3") (pintype "unspecified"))
    )
    (net (code "34") (name "Net-(Q10-C)") (class "Default")
      (node (ref "C8") (pin "2") (pinfunction "2_2") (pintype "input"))
      (node (ref "OUT_3_5_V") (pin "2") (pinfunction "2_2") (pintype "unspecified"))
      (node (ref "Q10") (pin "1") (pinfunction "C_1") (pintype "unspecified"))
      (node (ref "R18") (pin "1") (pinfunction "1_1") (pintype "unspecified"))
      (node (ref "SG1") (pin "-") (pinfunction "2_-") (pintype "unspecified"))
    )
    (net (code "35") (name "Net-(Q11-B)") (class "Default")
      (node (ref "Q11") (pin "2") (pinfunction "B_2") (pintype "unspecified"))
      (node (ref "R27") (pin "1") (pinfunction "1_1") (pintype "unspecified"))
    )
    (net (code "36") (name "Net-(Q11-C)") (class "Default")
      (node (ref "Q11") (pin "1") (pinfunction "C_1") (pintype "unspecified"))
      (node (ref "Q15") (pin "2") (pinfunction "B_2") (pintype "unspecified"))
      (node (ref "Q16") (pin "1") (pinfunction "C_1") (pintype "unspecified"))
      (node (ref "R28") (pin "2") (pinfunction "2_2") (pintype "unspecified"))
    )
    (net (code "37") (name "Net-(Q12-D)") (class "Default")
      (node (ref "C13") (pin "1") (pinfunction "1_1") (pintype "input"))
      (node (ref "Q12") (pin "2") (pinfunction "D_2") (pintype "unspecified"))
      (node (ref "Q7") (pin "3") (pinfunction "S_3") (pintype "unspecified"))
      (node (ref "SILOWNIKI") (pin "1") (pinfunction "1_1") (pintype "unspecified"))
    )
    (net (code "38") (name "Net-(Q12-G)") (class "Default")
      (node (ref "Q12") (pin "1") (pinfunction "G_1") (pintype "unspecified"))
      (node (ref "Q13") (pin "1") (pinfunction "C_1") (pintype "unspecified"))
      (node (ref "Q18") (pin "1") (pinfunction "G_1") (pintype "unspecified"))
      (node (ref "R25") (pin "2") (pinfunction "2_2") (pintype "unspecified"))
    )
    (net (code "39") (name "Net-(Q12-S)") (class "Default")
      (node (ref "C11") (pin "2") (pinfunction "2_2") (pintype "unspecified"))
      (node (ref "Q12") (pin "3") (pinfunction "S_3") (pintype "unspecified"))
      (node (ref "Q13") (pin "3") (pinfunction "E_3") (pintype "unspecified"))
      (node (ref "Q14") (pin "2") (pinfunction "D_2") (pintype "unspecified"))
      (node (ref "Q17") (pin "3") (pinfunction "E_3") (pintype "unspecified"))
      (node (ref "Q2") (pin "3") (pinfunction "S_3") (pintype "unspecified"))
      (node (ref "Q5") (pin "3") (pinfunction "E_3") (pintype "unspecified"))
      (node (ref "Q6") (pin "3") (pinfunction "E_3") (pintype "unspecified"))
    )
    (net (code "40") (name "Net-(Q13-B)") (class "Default")
      (node (ref "Q13") (pin "2") (pinfunction "B_2") (pintype "unspecified"))
      (node (ref "Q17") (pin "1") (pinfunction "C_1") (pintype "unspecified"))
      (node (ref "R26") (pin "2") (pinfunction "2_2") (pintype "unspecified"))
    )
    (net (code "41") (name "Net-(Q14-G)") (class "Default")
      (node (ref "Q14") (pin "1") (pinfunction "G_1") (pintype "unspecified"))
      (node (ref "Q15") (pin "1") (pinfunction "C_1") (pintype "unspecified"))
      (node (ref "R29") (pin "2") (pinfunction "2_2") (pintype "unspecified"))
    )
    (net (code "42") (name "Net-(Q16-B)") (class "Default")
      (node (ref "Q16") (pin "2") (pinfunction "B_2") (pintype "unspecified"))
      (node (ref "R30") (pin "1") (pinfunction "1_1") (pintype "unspecified"))
    )
    (net (code "43") (name "Net-(Q17-B)") (class "Default")
      (node (ref "Q17") (pin "2") (pinfunction "B_2") (pintype "unspecified"))
      (node (ref "R31") (pin "1") (pinfunction "1_1") (pintype "unspecified"))
    )
    (net (code "44") (name "Net-(Q18-S)") (class "Default")
      (node (ref "C13") (pin "2") (pinfunction "2_2") (pintype "input"))
      (node (ref "Q18") (pin "3") (pinfunction "S_3") (pintype "unspecified"))
      (node (ref "Q2") (pin "2") (pinfunction "D_2") (pintype "unspecified"))
      (node (ref "SILOWNIKI") (pin "2") (pinfunction "2_2") (pintype "unspecified"))
    )
    (net (code "45") (name "Net-(R12-Pad2)") (class "Default")
      (node (ref "R12") (pin "2") (pinfunction "2_2") (pintype "unspecified"))
      (node (ref "U4") (pin "1") (pinfunction "1_1") (pintype "unspecified"))
    )
    (net (code "46") (name "Net-(R13-Pad2)") (class "Default")
      (node (ref "R13") (pin "2") (pinfunction "2_2") (pintype "unspecified"))
      (node (ref "U2") (pin "1") (pinfunction "1_1") (pintype "unspecified"))
    )
    (net (code "47") (name "Net-(R17-Pad2)") (class "Default")
      (node (ref "R17") (pin "2") (pinfunction "2_2") (pintype "unspecified"))
      (node (ref "U5") (pin "1") (pinfunction "1_1") (pintype "unspecified"))
    )
    (net (code "48") (name "Net-(R20-Pad1)") (class "Default")
      (node (ref "R20") (pin "1") (pinfunction "1_1") (pintype "unspecified"))
      (node (ref "U2") (pin "4") (pinfunction "4_4") (pintype "unspecified"))
    )
    (net (code "49") (name "Net-(R23-Pad1)") (class "Default")
      (node (ref "R23") (pin "1") (pinfunction "1_1") (pintype "unspecified"))
      (node (ref "U4") (pin "4") (pinfunction "4_4") (pintype "unspecified"))
    )
    (net (code "50") (name "Net-(R32-Pad2)") (class "Default")
      (node (ref "R32") (pin "2") (pinfunction "2_2") (pintype "unspecified"))
      (node (ref "U3") (pin "1") (pinfunction "1_1") (pintype "unspecified"))
    )
    (net (code "51") (name "Net-(R33-Pad1)") (class "Default")
      (node (ref "R33") (pin "1") (pinfunction "1_1") (pintype "unspecified"))
      (node (ref "U3") (pin "4") (pinfunction "4_4") (pintype "unspecified"))
    )
    (net (code "52") (name "Net-(R34-Pad1)") (class "Default")
      (node (ref "R34") (pin "1") (pinfunction "1_1") (pintype "unspecified"))
      (node (ref "U5") (pin "3") (pinfunction "3_3") (pintype "unspecified"))
    )
    (net (code "53") (name "Net-(R35-Pad2)") (class "Default")
      (node (ref "R35") (pin "2") (pinfunction "2_2") (pintype "unspecified"))
      (node (ref "U6") (pin "1") (pinfunction "1_1") (pintype "unspecified"))
    )
    (net (code "54") (name "Net-(R36-Pad2)") (class "Default")
      (node (ref "R36") (pin "2") (pinfunction "2_2") (pintype "unspecified"))
      (node (ref "U8") (pin "1") (pinfunction "1_1") (pintype "unspecified"))
    )
    (net (code "55") (name "Net-(R37-Pad1)") (class "Default")
      (node (ref "R37") (pin "1") (pinfunction "1_1") (pintype "unspecified"))
      (node (ref "U8") (pin "3") (pinfunction "3_3") (pintype "unspecified"))
    )
    (net (code "56") (name "Net-(R38-Pad1)") (class "Default")
      (node (ref "R38") (pin "1") (pinfunction "1_1") (pintype "unspecified"))
      (node (ref "U6") (pin "3") (pinfunction "3_3") (pintype "unspecified"))
    )
    (net (code "57") (name "Net-(SG1-1)") (class "Default")
      (node (ref "H2") (pin "2") (pinfunction "2_2") (pintype "unspecified"))
      (node (ref "SG1") (pin "+") (pinfunction "1_+") (pintype "unspecified"))
    )
    (net (code "58") (name "Net-(U7-A)") (class "Default")
      (node (ref "D4") (pin "C") (pinfunction "C_C") (pintype "bidirectional"))
      (node (ref "D5") (pin "1") (pinfunction "1_1") (pintype "unspecified"))
      (node (ref "R14") (pin "1") (pinfunction "1_1") (pintype "unspecified"))
      (node (ref "RS485") (pin "1") (pinfunction "1_1") (pintype "unspecified"))
      (node (ref "U7") (pin "6") (pinfunction "A_6") (pintype "unspecified"))
    )
    (net (code "59") (name "Net-(U7-B)") (class "Default")
      (node (ref "D3") (pin "C") (pinfunction "C_C") (pintype "bidirectional"))
      (node (ref "D5") (pin "2") (pinfunction "2_2") (pintype "unspecified"))
      (node (ref "R14") (pin "2") (pinfunction "2_2") (pintype "unspecified"))
      (node (ref "RS485") (pin "2") (pinfunction "2_2") (pintype "unspecified"))
      (node (ref "U7") (pin "7") (pinfunction "B_7") (pintype "unspecified"))
    )
    (net (code "60") (name "Net-(U11-Pad2)") (class "Default")
      (node (ref "U11") (pin "2") (pinfunction "2_2") (pintype "unspecified"))
      (node (ref "ZASILANIE") (pin "2") (pinfunction "2_2") (pintype "unspecified"))
    )
    (net (code "61") (name "unconnected-(24C32-A0-Pad1)") (class "Default")
      (node (ref "24C32") (pin "1") (pinfunction "A0_1") (pintype "unspecified"))
    )
    (net (code "62") (name "unconnected-(24C32-A1-Pad2)") (class "Default")
      (node (ref "24C32") (pin "2") (pinfunction "A1_2") (pintype "unspecified"))
    )
    (net (code "63") (name "unconnected-(24C32-A2-Pad3)") (class "Default")
      (node (ref "24C32") (pin "3") (pinfunction "A2_3") (pintype "unspecified"))
    )
    (net (code "64") (name "unconnected-(24C32-WP-Pad7)") (class "Default")
      (node (ref "24C32") (pin "7") (pinfunction "WP_7") (pintype "unspecified"))
    )
    (net (code "65") (name "unconnected-(ESP1-5v-Pad1)") (class "Default")
      (node (ref "ESP1") (pin "1") (pinfunction "5v_1") (pintype "unspecified"))
    )
    (net (code "66") (name "unconnected-(ESP1-D3-Pad13)") (class "Default")
      (node (ref "ESP1") (pin "13") (pinfunction "D3_13") (pintype "unspecified"))
    )
    (net (code "67") (name "unconnected-(ESP1-D4-Pad19)") (class "Default")
      (node (ref "ESP1") (pin "19") (pinfunction "D4_19") (pintype "unspecified"))
    )
    (net (code "68") (name "unconnected-(ESP1-D8-Pad25)") (class "Default")
      (node (ref "ESP1") (pin "25") (pinfunction "D8_25") (pintype "unspecified"))
    )
    (net (code "69") (name "unconnected-(ESP1-D9-Pad3)") (class "Default")
      (node (ref "ESP1") (pin "3") (pinfunction "D9_3") (pintype "unspecified"))
    )
    (net (code "70") (name "unconnected-(ESP1-D12-Pad28)") (class "Default")
      (node (ref "ESP1") (pin "28") (pinfunction "D12_28") (pintype "unspecified"))
    )
    (net (code "71") (name "unconnected-(ESP1-D13-Pad29)") (class "Default")
      (node (ref "ESP1") (pin "29") (pinfunction "D13_29") (pintype "unspecified"))
    )
    (net (code "72") (name "unconnected-(ESP1-D15-Pad10)") (class "Default")
      (node (ref "ESP1") (pin "10") (pinfunction "D15_10") (pintype "unspecified"))
    )
    (net (code "73") (name "unconnected-(ESP1-GND-Pad2)") (class "Default")
      (node (ref "ESP1") (pin "2") (pinfunction "GND_2") (pintype "unspecified"))
    )
    (net (code "74") (name "unconnected-(ESP1-GND-Pad16)") (class "Default")
      (node (ref "ESP1") (pin "16") (pinfunction "GND_16") (pintype "unspecified"))
    )
    (net (code "75") (name "unconnected-(ESP1-RST-Pad18)") (class "Default")
      (node (ref "ESP1") (pin "18") (pinfunction "RST_18") (pintype "unspecified"))
    )
    (net (code "76") (name "unconnected-(ESP1-RX-Pad11)") (class "Default")
      (node (ref "ESP1") (pin "11") (pinfunction "RX_11") (pintype "unspecified"))
    )
    (net (code "77") (name "unconnected-(ESP1-TX-Pad12)") (class "Default")
      (node (ref "ESP1") (pin "12") (pinfunction "TX_12") (pintype "unspecified"))
    )
  )
)
